# umodular_mix4.net
KiCad netlist of a schematic drawn in EAGLE
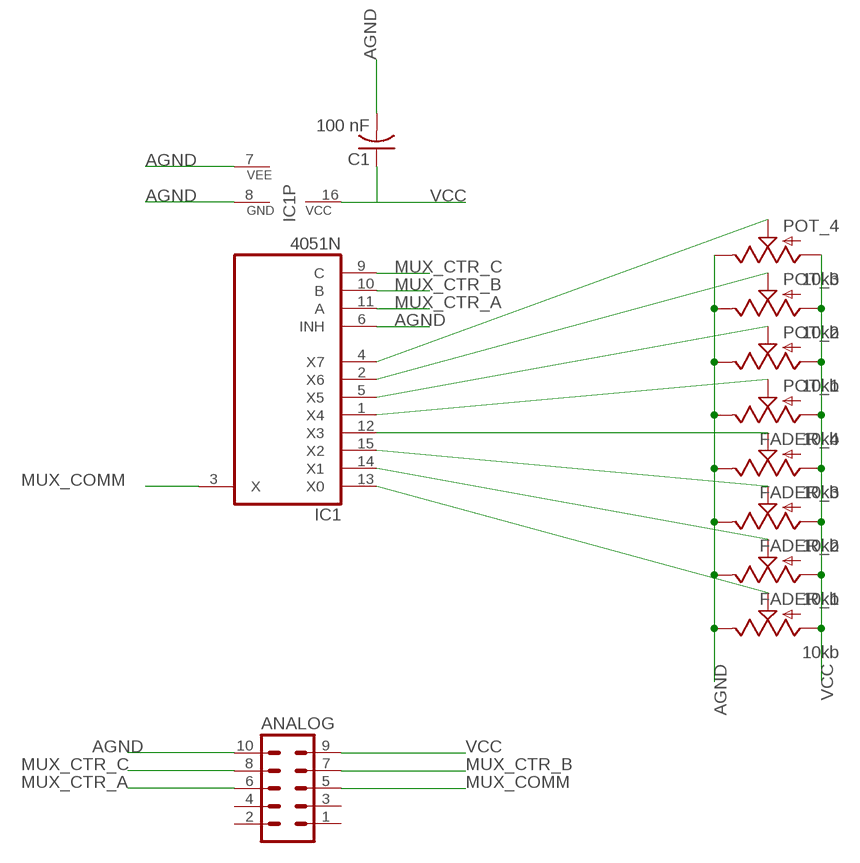
[diagram p0: schematic, sheet 1]
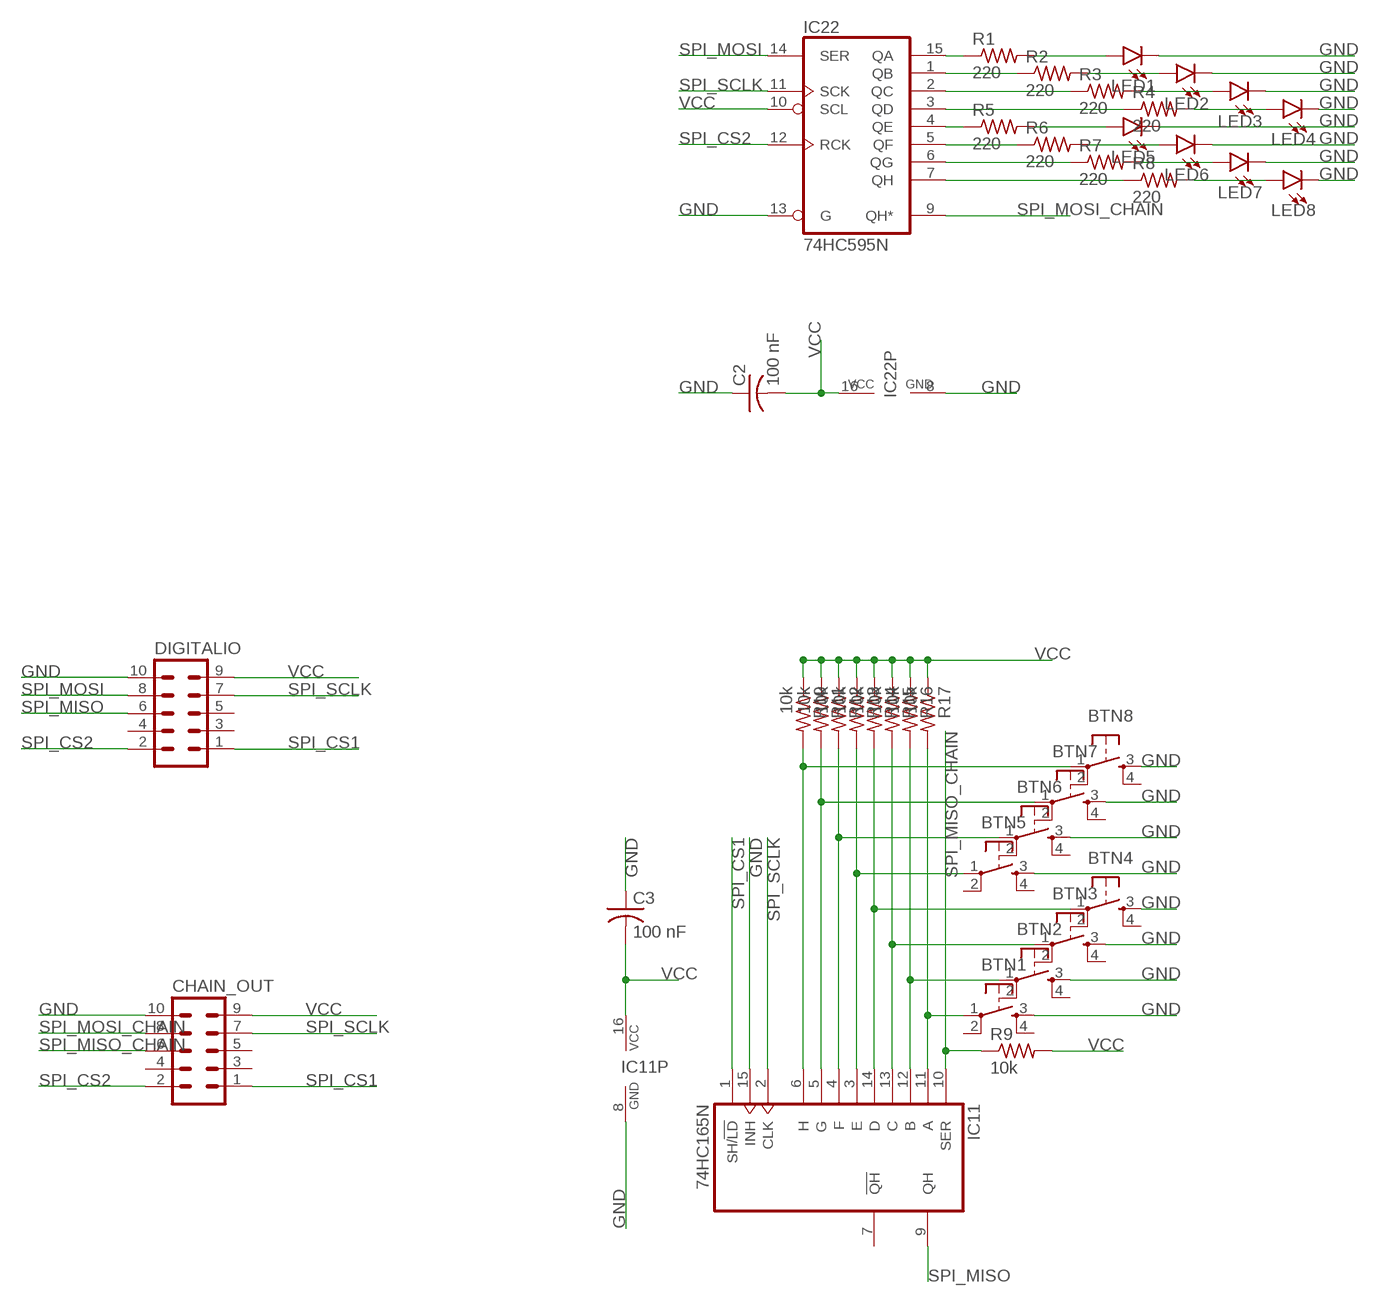
[diagram p1: schematic, sheet 2]

(export (version "E")
  (design (tool "Eeschema 10.0.6"))
  (components
    (comp (ref "ANALOG")
      (value "MA05-2")
      (footprint "eagle-import:MA05-2")
      (libsource (lib "eagle-import") (part "MA05-2"))
    )
    (comp (ref "C1")
      (value "100 nF")
      (footprint "eagle-import:C050-024X044")
      (libsource (lib "eagle-import") (part "C-US050-024X044"))
    )
    (comp (ref "FADER_1")
      (value "10kb")
      (footprint "eagle-import:SLIDER")
      (libsource (lib "eagle-import") (part "SLIDER"))
    )
    (comp (ref "FADER_2")
      (value "10kb")
      (footprint "eagle-import:SLIDER")
      (libsource (lib "eagle-import") (part "SLIDER"))
    )
    (comp (ref "FADER_3")
      (value "10kb")
      (footprint "eagle-import:SLIDER")
      (libsource (lib "eagle-import") (part "SLIDER"))
    )
    (comp (ref "FADER_4")
      (value "10kb")
      (footprint "eagle-import:SLIDER")
      (libsource (lib "eagle-import") (part "SLIDER"))
    )
    (comp (ref "IC1")
      (value "4051N")
      (footprint "eagle-import:DIL16")
      (libsource (lib "eagle-import") (part "4051N"))
    )
    (comp (ref "POT_1")
      (value "10kb")
      (footprint "eagle-import:ALPS_POT")
      (libsource (lib "eagle-import") (part "POT"))
    )
    (comp (ref "POT_2")
      (value "10kb")
      (footprint "eagle-import:ALPS_POT")
      (libsource (lib "eagle-import") (part "POT"))
    )
    (comp (ref "POT_3")
      (value "10kb")
      (footprint "eagle-import:ALPS_POT")
      (libsource (lib "eagle-import") (part "POT"))
    )
    (comp (ref "POT_4")
      (value "10kb")
      (footprint "eagle-import:ALPS_POT")
      (libsource (lib "eagle-import") (part "POT"))
    )
    (comp (ref "BTN1")
      (value "TAC_SWITCHPTH")
      (footprint "eagle-import:TACTILE-PTH")
      (libsource (lib "eagle-import") (part "TAC_SWITCHPTH"))
    )
    (comp (ref "BTN2")
      (value "TAC_SWITCHPTH")
      (footprint "eagle-import:TACTILE-PTH")
      (libsource (lib "eagle-import") (part "TAC_SWITCHPTH"))
    )
    (comp (ref "BTN3")
      (value "TAC_SWITCHPTH")
      (footprint "eagle-import:TACTILE-PTH")
      (libsource (lib "eagle-import") (part "TAC_SWITCHPTH"))
    )
    (comp (ref "BTN4")
      (value "TAC_SWITCHPTH")
      (footprint "eagle-import:TACTILE-PTH")
      (libsource (lib "eagle-import") (part "TAC_SWITCHPTH"))
    )
    (comp (ref "BTN5")
      (value "TAC_SWITCHPTH")
      (footprint "eagle-import:TACTILE-PTH")
      (libsource (lib "eagle-import") (part "TAC_SWITCHPTH"))
    )
    (comp (ref "BTN6")
      (value "TAC_SWITCHPTH")
      (footprint "eagle-import:TACTILE-PTH")
      (libsource (lib "eagle-import") (part "TAC_SWITCHPTH"))
    )
    (comp (ref "BTN7")
      (value "TAC_SWITCHPTH")
      (footprint "eagle-import:TACTILE-PTH")
      (libsource (lib "eagle-import") (part "TAC_SWITCHPTH"))
    )
    (comp (ref "BTN8")
      (value "TAC_SWITCHPTH")
      (footprint "eagle-import:TACTILE-PTH")
      (libsource (lib "eagle-import") (part "TAC_SWITCHPTH"))
    )
    (comp (ref "C2")
      (value "100 nF")
      (footprint "eagle-import:C050-024X044")
      (libsource (lib "eagle-import") (part "C-US050-024X044"))
    )
    (comp (ref "C3")
      (value "100 nF")
      (footprint "eagle-import:C050-024X044")
      (libsource (lib "eagle-import") (part "C-US050-024X044"))
    )
    (comp (ref "CHAIN_OUT")
      (value "MA05-2")
      (footprint "eagle-import:MA05-2")
      (libsource (lib "eagle-import") (part "MA05-2"))
    )
    (comp (ref "DIGITALIO")
      (value "MA05-2")
      (footprint "eagle-import:MA05-2")
      (libsource (lib "eagle-import") (part "MA05-2"))
    )
    (comp (ref "IC11")
      (value "74HC165N")
      (footprint "eagle-import:DIL16")
      (libsource (lib "eagle-import") (part "74165NHC"))
    )
    (comp (ref "IC22")
      (value "74HC595N")
      (footprint "eagle-import:DIL16")
      (libsource (lib "eagle-import") (part "74595NHC"))
    )
    (comp (ref "LED1")
      (value "LED3MM")
      (footprint "eagle-import:LED_3MM")
      (libsource (lib "eagle-import") (part "LED3MM"))
    )
    (comp (ref "LED2")
      (value "LED3MM")
      (footprint "eagle-import:LED_3MM")
      (libsource (lib "eagle-import") (part "LED3MM"))
    )
    (comp (ref "LED3")
      (value "LED3MM")
      (footprint "eagle-import:LED_3MM")
      (libsource (lib "eagle-import") (part "LED3MM"))
    )
    (comp (ref "LED4")
      (value "LED3MM")
      (footprint "eagle-import:LED_3MM")
      (libsource (lib "eagle-import") (part "LED3MM"))
    )
    (comp (ref "LED5")
      (value "LED3MM")
      (footprint "eagle-import:LED_3MM")
      (libsource (lib "eagle-import") (part "LED3MM"))
    )
    (comp (ref "LED6")
      (value "LED3MM")
      (footprint "eagle-import:LED_3MM")
      (libsource (lib "eagle-import") (part "LED3MM"))
    )
    (comp (ref "LED7")
      (value "LED3MM")
      (footprint "eagle-import:LED_3MM")
      (libsource (lib "eagle-import") (part "LED3MM"))
    )
    (comp (ref "LED8")
      (value "LED3MM")
      (footprint "eagle-import:LED_3MM")
      (libsource (lib "eagle-import") (part "LED3MM"))
    )
    (comp (ref "R1")
      (value "220")
      (footprint "eagle-import:0204_7")
      (libsource (lib "eagle-import") (part "R-US_0204/7"))
    )
    (comp (ref "R2")
      (value "220")
      (footprint "eagle-import:0204_7")
      (libsource (lib "eagle-import") (part "R-US_0204/7"))
    )
    (comp (ref "R3")
      (value "220")
      (footprint "eagle-import:0204_7")
      (libsource (lib "eagle-import") (part "R-US_0204/7"))
    )
    (comp (ref "R4")
      (value "220")
      (footprint "eagle-import:0204_7")
      (libsource (lib "eagle-import") (part "R-US_0204/7"))
    )
    (comp (ref "R5")
      (value "220")
      (footprint "eagle-import:0204_7")
      (libsource (lib "eagle-import") (part "R-US_0204/7"))
    )
    (comp (ref "R6")
      (value "220")
      (footprint "eagle-import:0204_7")
      (libsource (lib "eagle-import") (part "R-US_0204/7"))
    )
    (comp (ref "R7")
      (value "220")
      (footprint "eagle-import:0204_7")
      (libsource (lib "eagle-import") (part "R-US_0204/7"))
    )
    (comp (ref "R8")
      (value "220")
      (footprint "eagle-import:0204_7")
      (libsource (lib "eagle-import") (part "R-US_0204/7"))
    )
    (comp (ref "R9")
      (value "10k")
      (footprint "eagle-import:0204_7")
      (libsource (lib "eagle-import") (part "resistor_R-US_0204/7"))
    )
    (comp (ref "R10")
      (value "10k")
      (footprint "eagle-import:0204_7")
      (libsource (lib "eagle-import") (part "resistor_R-US_0204/7"))
    )
    (comp (ref "R11")
      (value "10k")
      (footprint "eagle-import:0204_7")
      (libsource (lib "eagle-import") (part "resistor_R-US_0204/7"))
    )
    (comp (ref "R12")
      (value "10k")
      (footprint "eagle-import:0204_7")
      (libsource (lib "eagle-import") (part "resistor_R-US_0204/7"))
    )
    (comp (ref "R13")
      (value "10k")
      (footprint "eagle-import:0204_7")
      (libsource (lib "eagle-import") (part "resistor_R-US_0204/7"))
    )
    (comp (ref "R14")
      (value "10k")
      (footprint "eagle-import:0204_7")
      (libsource (lib "eagle-import") (part "resistor_R-US_0204/7"))
    )
    (comp (ref "R15")
      (value "10k")
      (footprint "eagle-import:0204_7")
      (libsource (lib "eagle-import") (part "resistor_R-US_0204/7"))
    )
    (comp (ref "R16")
      (value "10k")
      (footprint "eagle-import:0204_7")
      (libsource (lib "eagle-import") (part "resistor_R-US_0204/7"))
    )
    (comp (ref "R17")
      (value "10k")
      (footprint "eagle-import:0204_7")
      (libsource (lib "eagle-import") (part "resistor_R-US_0204/7"))
    )
  )
  (nets
    (net (code "1") (name "AGND") (class "Default")
      (node (ref "ANALOG") (pin "10") (pinfunction "10_10") (pintype "passive"))
      (node (ref "C1") (pin "2") (pinfunction "2_2") (pintype "passive"))
      (node (ref "FADER_1") (pin "1") (pinfunction "1_1") (pintype "passive"))
      (node (ref "FADER_2") (pin "1") (pinfunction "1_1") (pintype "passive"))
      (node (ref "FADER_3") (pin "1") (pinfunction "1_1") (pintype "passive"))
      (node (ref "FADER_4") (pin "1") (pinfunction "1_1") (pintype "passive"))
      (node (ref "IC1") (pin "6") (pinfunction "INH_6") (pintype "input"))
      (node (ref "IC1") (pin "7") (pinfunction "VEE_7") (pintype "power_in"))
      (node (ref "IC1") (pin "8") (pinfunction "GND_8") (pintype "power_in"))
      (node (ref "POT_1") (pin "P$1") (pinfunction "E_P$1") (pintype "passive"))
      (node (ref "POT_2") (pin "P$1") (pinfunction "E_P$1") (pintype "passive"))
      (node (ref "POT_3") (pin "P$1") (pinfunction "E_P$1") (pintype "passive"))
      (node (ref "POT_4") (pin "P$1") (pinfunction "E_P$1") (pintype "passive"))
    )
    (net (code "2") (name "GND") (class "Default")
      (node (ref "BTN1") (pin "3") (pinfunction "3_3") (pintype "passive"))
      (node (ref "BTN2") (pin "3") (pinfunction "3_3") (pintype "passive"))
      (node (ref "BTN3") (pin "3") (pinfunction "3_3") (pintype "passive"))
      (node (ref "BTN4") (pin "3") (pinfunction "3_3") (pintype "passive"))
      (node (ref "BTN5") (pin "3") (pinfunction "3_3") (pintype "passive"))
      (node (ref "BTN6") (pin "3") (pinfunction "3_3") (pintype "passive"))
      (node (ref "BTN7") (pin "3") (pinfunction "3_3") (pintype "passive"))
      (node (ref "BTN8") (pin "3") (pinfunction "3_3") (pintype "passive"))
      (node (ref "C2") (pin "1") (pinfunction "1_1") (pintype "passive"))
      (node (ref "C3") (pin "1") (pinfunction "1_1") (pintype "passive"))
      (node (ref "CHAIN_OUT") (pin "10") (pinfunction "10_10") (pintype "passive"))
      (node (ref "DIGITALIO") (pin "10") (pinfunction "10_10") (pintype "passive"))
      (node (ref "IC11") (pin "15") (pinfunction "INH_15") (pintype "input"))
      (node (ref "IC11") (pin "8") (pinfunction "GND_8") (pintype "power_in"))
      (node (ref "IC22") (pin "13") (pinfunction "G_13") (pintype "input"))
      (node (ref "IC22") (pin "8") (pinfunction "GND_8") (pintype "power_in"))
      (node (ref "LED1") (pin "K") (pinfunction "C_K") (pintype "passive"))
      (node (ref "LED2") (pin "K") (pinfunction "C_K") (pintype "passive"))
      (node (ref "LED3") (pin "K") (pinfunction "C_K") (pintype "passive"))
      (node (ref "LED4") (pin "K") (pinfunction "C_K") (pintype "passive"))
      (node (ref "LED5") (pin "K") (pinfunction "C_K") (pintype "passive"))
      (node (ref "LED6") (pin "K") (pinfunction "C_K") (pintype "passive"))
      (node (ref "LED7") (pin "K") (pinfunction "C_K") (pintype "passive"))
      (node (ref "LED8") (pin "K") (pinfunction "C_K") (pintype "passive"))
    )
    (net (code "3") (name "MUX_COMM") (class "Default")
      (node (ref "ANALOG") (pin "5") (pinfunction "5_5") (pintype "passive"))
      (node (ref "IC1") (pin "3") (pinfunction "X_3") (pintype "bidirectional"))
    )
    (net (code "4") (name "MUX_CTR_A") (class "Default")
      (node (ref "ANALOG") (pin "6") (pinfunction "6_6") (pintype "passive"))
      (node (ref "IC1") (pin "11") (pinfunction "A_11") (pintype "input"))
    )
    (net (code "5") (name "MUX_CTR_B") (class "Default")
      (node (ref "ANALOG") (pin "7") (pinfunction "7_7") (pintype "passive"))
      (node (ref "IC1") (pin "10") (pinfunction "B_10") (pintype "input"))
    )
    (net (code "6") (name "MUX_CTR_C") (class "Default")
      (node (ref "ANALOG") (pin "8") (pinfunction "8_8") (pintype "passive"))
      (node (ref "IC1") (pin "9") (pinfunction "C_9") (pintype "input"))
    )
    (net (code "7") (name "Net-(IC1A-X0)") (class "Default")
      (node (ref "FADER_1") (pin "2") (pinfunction "2_2") (pintype "passive"))
      (node (ref "IC1") (pin "13") (pinfunction "X0_13") (pintype "bidirectional"))
    )
    (net (code "8") (name "Net-(IC1A-X1)") (class "Default")
      (node (ref "FADER_2") (pin "2") (pinfunction "2_2") (pintype "passive"))
      (node (ref "IC1") (pin "14") (pinfunction "X1_14") (pintype "bidirectional"))
    )
    (net (code "9") (name "Net-(IC1A-X2)") (class "Default")
      (node (ref "FADER_3") (pin "2") (pinfunction "2_2") (pintype "passive"))
      (node (ref "IC1") (pin "15") (pinfunction "X2_15") (pintype "bidirectional"))
    )
    (net (code "10") (name "Net-(IC1A-X3)") (class "Default")
      (node (ref "FADER_4") (pin "2") (pinfunction "2_2") (pintype "passive"))
      (node (ref "IC1") (pin "12") (pinfunction "X3_12") (pintype "bidirectional"))
    )
    (net (code "11") (name "Net-(IC1A-X4)") (class "Default")
      (node (ref "IC1") (pin "1") (pinfunction "X4_1") (pintype "bidirectional"))
      (node (ref "POT_1") (pin "P$2") (pinfunction "S_P$2") (pintype "passive"))
    )
    (net (code "12") (name "Net-(IC1A-X5)") (class "Default")
      (node (ref "IC1") (pin "5") (pinfunction "X5_5") (pintype "bidirectional"))
      (node (ref "POT_2") (pin "P$2") (pinfunction "S_P$2") (pintype "passive"))
    )
    (net (code "13") (name "Net-(IC1A-X6)") (class "Default")
      (node (ref "IC1") (pin "2") (pinfunction "X6_2") (pintype "bidirectional"))
      (node (ref "POT_3") (pin "P$2") (pinfunction "S_P$2") (pintype "passive"))
    )
    (net (code "14") (name "Net-(IC1A-X7)") (class "Default")
      (node (ref "IC1") (pin "4") (pinfunction "X7_4") (pintype "bidirectional"))
      (node (ref "POT_4") (pin "P$2") (pinfunction "S_P$2") (pintype "passive"))
    )
    (net (code "15") (name "Net-(IC11A-A)") (class "Default")
      (node (ref "BTN1") (pin "1") (pinfunction "1_1") (pintype "passive"))
      (node (ref "IC11") (pin "11") (pinfunction "A_11") (pintype "input"))
      (node (ref "R17") (pin "2") (pinfunction "2_2") (pintype "passive"))
    )
    (net (code "16") (name "Net-(IC11A-B)") (class "Default")
      (node (ref "BTN2") (pin "1") (pinfunction "1_1") (pintype "passive"))
      (node (ref "IC11") (pin "12") (pinfunction "B_12") (pintype "input"))
      (node (ref "R16") (pin "2") (pinfunction "2_2") (pintype "passive"))
    )
    (net (code "17") (name "Net-(IC11A-C)") (class "Default")
      (node (ref "BTN3") (pin "1") (pinfunction "1_1") (pintype "passive"))
      (node (ref "IC11") (pin "13") (pinfunction "C_13") (pintype "input"))
      (node (ref "R15") (pin "2") (pinfunction "2_2") (pintype "passive"))
    )
    (net (code "18") (name "Net-(IC11A-D)") (class "Default")
      (node (ref "BTN4") (pin "1") (pinfunction "1_1") (pintype "passive"))
      (node (ref "IC11") (pin "14") (pinfunction "D_14") (pintype "input"))
      (node (ref "R14") (pin "2") (pinfunction "2_2") (pintype "passive"))
    )
    (net (code "19") (name "Net-(IC11A-E)") (class "Default")
      (node (ref "BTN5") (pin "1") (pinfunction "1_1") (pintype "passive"))
      (node (ref "IC11") (pin "3") (pinfunction "E_3") (pintype "input"))
      (node (ref "R13") (pin "2") (pinfunction "2_2") (pintype "passive"))
    )
    (net (code "20") (name "Net-(IC11A-F)") (class "Default")
      (node (ref "BTN6") (pin "1") (pinfunction "1_1") (pintype "passive"))
      (node (ref "IC11") (pin "4") (pinfunction "F_4") (pintype "input"))
      (node (ref "R12") (pin "2") (pinfunction "2_2") (pintype "passive"))
    )
    (net (code "21") (name "Net-(IC11A-G)") (class "Default")
      (node (ref "BTN7") (pin "1") (pinfunction "1_1") (pintype "passive"))
      (node (ref "IC11") (pin "5") (pinfunction "G_5") (pintype "input"))
      (node (ref "R11") (pin "2") (pinfunction "2_2") (pintype "passive"))
    )
    (net (code "22") (name "Net-(IC11A-H)") (class "Default")
      (node (ref "BTN8") (pin "1") (pinfunction "1_1") (pintype "passive"))
      (node (ref "IC11") (pin "6") (pinfunction "H_6") (pintype "input"))
      (node (ref "R10") (pin "2") (pinfunction "2_2") (pintype "passive"))
    )
    (net (code "23") (name "Net-(IC22A-QA)") (class "Default")
      (node (ref "IC22") (pin "15") (pinfunction "QA_15") (pintype "tri_state"))
      (node (ref "R1") (pin "1") (pinfunction "1_1") (pintype "passive"))
    )
    (net (code "24") (name "Net-(IC22A-QB)") (class "Default")
      (node (ref "IC22") (pin "1") (pinfunction "QB_1") (pintype "tri_state"))
      (node (ref "R2") (pin "1") (pinfunction "1_1") (pintype "passive"))
    )
    (net (code "25") (name "Net-(IC22A-QC)") (class "Default")
      (node (ref "IC22") (pin "2") (pinfunction "QC_2") (pintype "tri_state"))
      (node (ref "R3") (pin "1") (pinfunction "1_1") (pintype "passive"))
    )
    (net (code "26") (name "Net-(IC22A-QD)") (class "Default")
      (node (ref "IC22") (pin "3") (pinfunction "QD_3") (pintype "tri_state"))
      (node (ref "R4") (pin "1") (pinfunction "1_1") (pintype "passive"))
    )
    (net (code "27") (name "Net-(IC22A-QE)") (class "Default")
      (node (ref "IC22") (pin "4") (pinfunction "QE_4") (pintype "tri_state"))
      (node (ref "R5") (pin "1") (pinfunction "1_1") (pintype "passive"))
    )
    (net (code "28") (name "Net-(IC22A-QF)") (class "Default")
      (node (ref "IC22") (pin "5") (pinfunction "QF_5") (pintype "tri_state"))
      (node (ref "R6") (pin "1") (pinfunction "1_1") (pintype "passive"))
    )
    (net (code "29") (name "Net-(IC22A-QG)") (class "Default")
      (node (ref "IC22") (pin "6") (pinfunction "QG_6") (pintype "tri_state"))
      (node (ref "R7") (pin "1") (pinfunction "1_1") (pintype "passive"))
    )
    (net (code "30") (name "Net-(IC22A-QH)") (class "Default")
      (node (ref "IC22") (pin "7") (pinfunction "QH_7") (pintype "tri_state"))
      (node (ref "R8") (pin "1") (pinfunction "1_1") (pintype "passive"))
    )
    (net (code "31") (name "Net-(LED1-PadA)") (class "Default")
      (node (ref "LED1") (pin "A") (pinfunction "A_A") (pintype "passive"))
      (node (ref "R1") (pin "2") (pinfunction "2_2") (pintype "passive"))
    )
    (net (code "32") (name "Net-(LED2-PadA)") (class "Default")
      (node (ref "LED2") (pin "A") (pinfunction "A_A") (pintype "passive"))
      (node (ref "R2") (pin "2") (pinfunction "2_2") (pintype "passive"))
    )
    (net (code "33") (name "Net-(LED3-PadA)") (class "Default")
      (node (ref "LED3") (pin "A") (pinfunction "A_A") (pintype "passive"))
      (node (ref "R3") (pin "2") (pinfunction "2_2") (pintype "passive"))
    )
    (net (code "34") (name "Net-(LED4-PadA)") (class "Default")
      (node (ref "LED4") (pin "A") (pinfunction "A_A") (pintype "passive"))
      (node (ref "R4") (pin "2") (pinfunction "2_2") (pintype "passive"))
    )
    (net (code "35") (name "Net-(LED5-PadA)") (class "Default")
      (node (ref "LED5") (pin "A") (pinfunction "A_A") (pintype "passive"))
      (node (ref "R5") (pin "2") (pinfunction "2_2") (pintype "passive"))
    )
    (net (code "36") (name "Net-(LED6-PadA)") (class "Default")
      (node (ref "LED6") (pin "A") (pinfunction "A_A") (pintype "passive"))
      (node (ref "R6") (pin "2") (pinfunction "2_2") (pintype "passive"))
    )
    (net (code "37") (name "Net-(LED7-PadA)") (class "Default")
      (node (ref "LED7") (pin "A") (pinfunction "A_A") (pintype "passive"))
      (node (ref "R7") (pin "2") (pinfunction "2_2") (pintype "passive"))
    )
    (net (code "38") (name "Net-(LED8-PadA)") (class "Default")
      (node (ref "LED8") (pin "A") (pinfunction "A_A") (pintype "passive"))
      (node (ref "R8") (pin "2") (pinfunction "2_2") (pintype "passive"))
    )
    (net (code "39") (name "SPI_CS1") (class "Default")
      (node (ref "CHAIN_OUT") (pin "1") (pinfunction "1_1") (pintype "passive"))
      (node (ref "DIGITALIO") (pin "1") (pinfunction "1_1") (pintype "passive"))
      (node (ref "IC11") (pin "1") (pinfunction "SH/~{LD}_1") (pintype "input"))
    )
    (net (code "40") (name "SPI_CS2") (class "Default")
      (node (ref "CHAIN_OUT") (pin "2") (pinfunction "2_2") (pintype "passive"))
      (node (ref "DIGITALIO") (pin "2") (pinfunction "2_2") (pintype "passive"))
      (node (ref "IC22") (pin "12") (pinfunction "RCK_12") (pintype "input"))
    )
    (net (code "41") (name "SPI_MISO") (class "Default")
      (node (ref "DIGITALIO") (pin "6") (pinfunction "6_6") (pintype "passive"))
      (node (ref "IC11") (pin "9") (pinfunction "QH_9") (pintype "output"))
    )
    (net (code "42") (name "SPI_MISO_CHAIN") (class "Default")
      (node (ref "CHAIN_OUT") (pin "6") (pinfunction "6_6") (pintype "passive"))
      (node (ref "IC11") (pin "10") (pinfunction "SER_10") (pintype "input"))
      (node (ref "R9") (pin "1") (pinfunction "1_1") (pintype "passive"))
    )
    (net (code "43") (name "SPI_MOSI") (class "Default")
      (node (ref "DIGITALIO") (pin "8") (pinfunction "8_8") (pintype "passive"))
      (node (ref "IC22") (pin "14") (pinfunction "SER_14") (pintype "input"))
    )
    (net (code "44") (name "SPI_MOSI_CHAIN") (class "Default")
      (node (ref "CHAIN_OUT") (pin "8") (pinfunction "8_8") (pintype "passive"))
      (node (ref "IC22") (pin "9") (pinfunction "QH*_9") (pintype "tri_state"))
    )
    (net (code "45") (name "SPI_SCLK") (class "Default")
      (node (ref "CHAIN_OUT") (pin "7") (pinfunction "7_7") (pintype "passive"))
      (node (ref "DIGITALIO") (pin "7") (pinfunction "7_7") (pintype "passive"))
      (node (ref "IC11") (pin "2") (pinfunction "CLK_2") (pintype "input"))
      (node (ref "IC22") (pin "11") (pinfunction "SCK_11") (pintype "input"))
    )
    (net (code "46") (name "VCC") (class "Default")
      (node (ref "ANALOG") (pin "9") (pinfunction "9_9") (pintype "passive"))
      (node (ref "C1") (pin "1") (pinfunction "1_1") (pintype "passive"))
      (node (ref "C2") (pin "2") (pinfunction "2_2") (pintype "passive"))
      (node (ref "C3") (pin "2") (pinfunction "2_2") (pintype "passive"))
      (node (ref "CHAIN_OUT") (pin "9") (pinfunction "9_9") (pintype "passive"))
      (node (ref "DIGITALIO") (pin "9") (pinfunction "9_9") (pintype "passive"))
      (node (ref "FADER_1") (pin "3") (pinfunction "3_3") (pintype "passive"))
      (node (ref "FADER_2") (pin "3") (pinfunction "3_3") (pintype "passive"))
      (node (ref "FADER_3") (pin "3") (pinfunction "3_3") (pintype "passive"))
      (node (ref "FADER_4") (pin "3") (pinfunction "3_3") (pintype "passive"))
      (node (ref "IC1") (pin "16") (pinfunction "VCC_16") (pintype "power_in"))
      (node (ref "IC11") (pin "16") (pinfunction "VCC_16") (pintype "power_in"))
      (node (ref "IC22") (pin "10") (pinfunction "SCL_10") (pintype "input"))
      (node (ref "IC22") (pin "16") (pinfunction "VCC_16") (pintype "power_in"))
      (node (ref "POT_1") (pin "P$3") (pinfunction "A_P$3") (pintype "passive"))
      (node (ref "POT_2") (pin "P$3") (pinfunction "A_P$3") (pintype "passive"))
      (node (ref "POT_3") (pin "P$3") (pinfunction "A_P$3") (pintype "passive"))
      (node (ref "POT_4") (pin "P$3") (pinfunction "A_P$3") (pintype "passive"))
      (node (ref "R10") (pin "1") (pinfunction "1_1") (pintype "passive"))
      (node (ref "R11") (pin "1") (pinfunction "1_1") (pintype "passive"))
      (node (ref "R12") (pin "1") (pinfunction "1_1") (pintype "passive"))
      (node (ref "R13") (pin "1") (pinfunction "1_1") (pintype "passive"))
      (node (ref "R14") (pin "1") (pinfunction "1_1") (pintype "passive"))
      (node (ref "R15") (pin "1") (pinfunction "1_1") (pintype "passive"))
      (node (ref "R16") (pin "1") (pinfunction "1_1") (pintype "passive"))
      (node (ref "R17") (pin "1") (pinfunction "1_1") (pintype "passive"))
      (node (ref "R9") (pin "2") (pinfunction "2_2") (pintype "passive"))
    )
    (net (code "47") (name "unconnected-(ANALOG-Pad1)") (class "Default")
      (node (ref "ANALOG") (pin "1") (pinfunction "1_1") (pintype "passive"))
    )
    (net (code "48") (name "unconnected-(ANALOG-Pad2)") (class "Default")
      (node (ref "ANALOG") (pin "2") (pinfunction "2_2") (pintype "passive"))
    )
    (net (code "49") (name "unconnected-(ANALOG-Pad3)") (class "Default")
      (node (ref "ANALOG") (pin "3") (pinfunction "3_3") (pintype "passive"))
    )
    (net (code "50") (name "unconnected-(ANALOG-Pad4)") (class "Default")
      (node (ref "ANALOG") (pin "4") (pinfunction "4_4") (pintype "passive"))
    )
    (net (code "51") (name "unconnected-(BTN1-Pad2)") (class "Default")
      (node (ref "BTN1") (pin "2") (pinfunction "2_2") (pintype "passive"))
    )
    (net (code "52") (name "unconnected-(BTN1-Pad4)") (class "Default")
      (node (ref "BTN1") (pin "4") (pinfunction "4_4") (pintype "passive"))
    )
    (net (code "53") (name "unconnected-(BTN2-Pad2)") (class "Default")
      (node (ref "BTN2") (pin "2") (pinfunction "2_2") (pintype "passive"))
    )
    (net (code "54") (name "unconnected-(BTN2-Pad4)") (class "Default")
      (node (ref "BTN2") (pin "4") (pinfunction "4_4") (pintype "passive"))
    )
    (net (code "55") (name "unconnected-(BTN3-Pad2)") (class "Default")
      (node (ref "BTN3") (pin "2") (pinfunction "2_2") (pintype "passive"))
    )
    (net (code "56") (name "unconnected-(BTN3-Pad4)") (class "Default")
      (node (ref "BTN3") (pin "4") (pinfunction "4_4") (pintype "passive"))
    )
    (net (code "57") (name "unconnected-(BTN4-Pad2)") (class "Default")
      (node (ref "BTN4") (pin "2") (pinfunction "2_2") (pintype "passive"))
    )
    (net (code "58") (name "unconnected-(BTN4-Pad4)") (class "Default")
      (node (ref "BTN4") (pin "4") (pinfunction "4_4") (pintype "passive"))
    )
    (net (code "59") (name "unconnected-(BTN5-Pad2)") (class "Default")
      (node (ref "BTN5") (pin "2") (pinfunction "2_2") (pintype "passive"))
    )
    (net (code "60") (name "unconnected-(BTN5-Pad4)") (class "Default")
      (node (ref "BTN5") (pin "4") (pinfunction "4_4") (pintype "passive"))
    )
    (net (code "61") (name "unconnected-(BTN6-Pad2)") (class "Default")
      (node (ref "BTN6") (pin "2") (pinfunction "2_2") (pintype "passive"))
    )
    (net (code "62") (name "unconnected-(BTN6-Pad4)") (class "Default")
      (node (ref "BTN6") (pin "4") (pinfunction "4_4") (pintype "passive"))
    )
    (net (code "63") (name "unconnected-(BTN7-Pad2)") (class "Default")
      (node (ref "BTN7") (pin "2") (pinfunction "2_2") (pintype "passive"))
    )
    (net (code "64") (name "unconnected-(BTN7-Pad4)") (class "Default")
      (node (ref "BTN7") (pin "4") (pinfunction "4_4") (pintype "passive"))
    )
    (net (code "65") (name "unconnected-(BTN8-Pad2)") (class "Default")
      (node (ref "BTN8") (pin "2") (pinfunction "2_2") (pintype "passive"))
    )
    (net (code "66") (name "unconnected-(BTN8-Pad4)") (class "Default")
      (node (ref "BTN8") (pin "4") (pinfunction "4_4") (pintype "passive"))
    )
    (net (code "67") (name "unconnected-(CHAIN_OUT-Pad3)") (class "Default")
      (node (ref "CHAIN_OUT") (pin "3") (pinfunction "3_3") (pintype "passive"))
    )
    (net (code "68") (name "unconnected-(CHAIN_OUT-Pad4)") (class "Default")
      (node (ref "CHAIN_OUT") (pin "4") (pinfunction "4_4") (pintype "passive"))
    )
    (net (code "69") (name "unconnected-(CHAIN_OUT-Pad5)") (class "Default")
      (node (ref "CHAIN_OUT") (pin "5") (pinfunction "5_5") (pintype "passive"))
    )
    (net (code "70") (name "unconnected-(DIGITALIO-Pad3)") (class "Default")
      (node (ref "DIGITALIO") (pin "3") (pinfunction "3_3") (pintype "passive"))
    )
    (net (code "71") (name "unconnected-(DIGITALIO-Pad4)") (class "Default")
      (node (ref "DIGITALIO") (pin "4") (pinfunction "4_4") (pintype "passive"))
    )
    (net (code "72") (name "unconnected-(DIGITALIO-Pad5)") (class "Default")
      (node (ref "DIGITALIO") (pin "5") (pinfunction "5_5") (pintype "passive"))
    )
    (net (code "73") (name "unconnected-(IC11A-~{QH}-Pad7)") (class "Default")
      (node (ref "IC11") (pin "7") (pinfunction "~{QH}_7") (pintype "output"))
    )
  )
)
